# Sterownik_pralnia.net
KiCad netlist of a schematic drawn in EAGLE
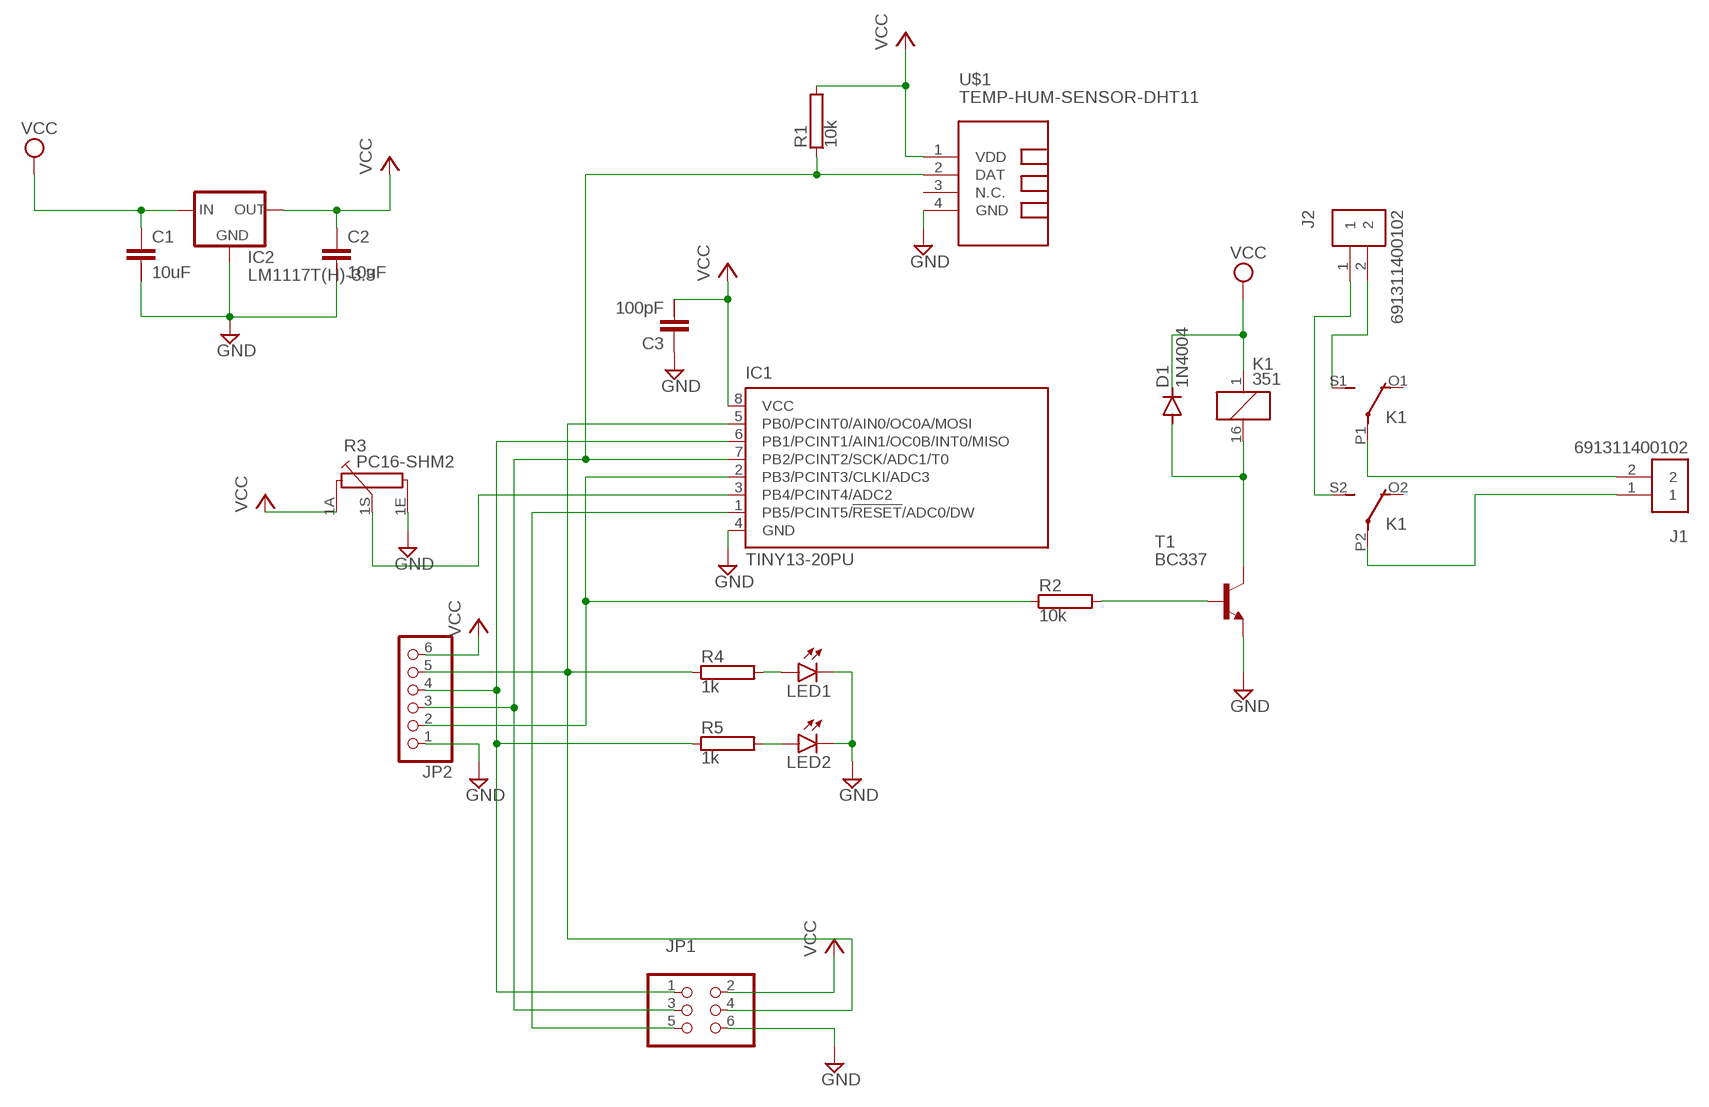
[diagram p0: schematic, sheet 1]

(export (version "E")
  (design (tool "Eeschema 10.0.6"))
  (components
    (comp (ref "C1")
      (value "10uF")
      (footprint "eagle-import:C2.5_5-2")
      (libsource (lib "eagle-import") (part "C-2.5-5/2"))
    )
    (comp (ref "C2")
      (value "10uF")
      (footprint "eagle-import:C2.5_5-2")
      (libsource (lib "eagle-import") (part "C-2.5-5/2"))
    )
    (comp (ref "C3")
      (value "100pF")
      (footprint "eagle-import:C2.5_5-2")
      (libsource (lib "eagle-import") (part "C-2.5-5/2"))
    )
    (comp (ref "D1")
      (value "1N4004")
      (footprint "eagle-import:DO41-10")
      (libsource (lib "eagle-import") (part "1N4004"))
    )
    (comp (ref "IC1")
      (value "TINY13-20PU")
      (footprint "eagle-import:DIL08")
      (fields (field (name "MPN") "ATTINY13-20PU"))
      (libsource (lib "eagle-import") (part "TINY13PU-20"))
    )
    (comp (ref "IC2")
      (value "LM1117T(H)-3.3")
      (footprint "eagle-import:TO220H")
      (fields (field (name "MF") "Texas Instruments") (field (name "MPN") "LM1117T-3.3"))
      (libsource (lib "eagle-import") (part "LM1117?-T(H)3.3"))
    )
    (comp (ref "J1")
      (value "691311400102")
      (footprint "eagle-import:TERMINALBLOCK_PLUGGABLE-2-7.62MM")
      (fields
        (field (name "DIGIKEY_PART_NO") "732-2823-ND")
        (field (name "MANUFACTURER") "WURTH ELEKTRONIK")
        (field (name "CREATED_BY") "PCBLayout.com")
      )
      (libsource (lib "eagle-import") (part "691311400102"))
    )
    (comp (ref "J2")
      (value "691311400102")
      (footprint "eagle-import:TERMINALBLOCK_PLUGGABLE-2-7.62MM")
      (fields
        (field (name "DIGIKEY_PART_NO") "732-2823-ND")
        (field (name "MANUFACTURER") "WURTH ELEKTRONIK")
        (field (name "CREATED_BY") "PCBLayout.com")
      )
      (libsource (lib "eagle-import") (part "691311400102"))
    )
    (comp (ref "JP1")
      (value "PINHD-2X3")
      (footprint "eagle-import:2X03")
      (libsource (lib "eagle-import") (part "PINHD-2X3"))
    )
    (comp (ref "JP2")
      (value "PINHD-1X6")
      (footprint "eagle-import:1X06")
      (libsource (lib "eagle-import") (part "PINHD-1X6"))
    )
    (comp (ref "K1")
      (value "351")
      (footprint "eagle-import:351")
      (libsource (lib "eagle-import") (part "351"))
    )
    (comp (ref "LED1")
      (value "LEDB152")
      (footprint "eagle-import:Q62902-B152")
      (libsource (lib "eagle-import") (part "LEDB152"))
    )
    (comp (ref "LED2")
      (value "LEDB152")
      (footprint "eagle-import:Q62902-B152")
      (libsource (lib "eagle-import") (part "LEDB152"))
    )
    (comp (ref "R1")
      (value "10k")
      (footprint "eagle-import:AC01")
      (libsource (lib "eagle-import") (part "RAC01"))
    )
    (comp (ref "R2")
      (value "10k")
      (footprint "eagle-import:AC01")
      (libsource (lib "eagle-import") (part "RAC01"))
    )
    (comp (ref "R3")
      (value "PC16-SHM2")
      (footprint "eagle-import:PC16-SHM2")
      (libsource (lib "eagle-import") (part "PC16-SHM2"))
    )
    (comp (ref "R4")
      (value "1k")
      (footprint "eagle-import:AC01")
      (libsource (lib "eagle-import") (part "RAC01"))
    )
    (comp (ref "R5")
      (value "1k")
      (footprint "eagle-import:AC01")
      (libsource (lib "eagle-import") (part "RAC01"))
    )
    (comp (ref "T1")
      (value "BC337")
      (footprint "eagle-import:TO92")
      (libsource (lib "eagle-import") (part "BC337"))
    )
    (comp (ref "U$1")
      (value "TEMP-HUM-SENSOR-DHT11")
      (footprint "eagle-import:TEMP-HUM-SENSOR-DHT11")
      (libsource (lib "eagle-import") (part "TEMP-HUM-SENSOR-DHT11"))
    )
  )
  (nets
    (net (code "1") (name "GND") (class "Default")
      (node (ref "C1") (pin "2") (pinfunction "2_2") (pintype "passive"))
      (node (ref "C2") (pin "2") (pinfunction "2_2") (pintype "passive"))
      (node (ref "C3") (pin "1") (pinfunction "1_1") (pintype "passive"))
      (node (ref "IC1") (pin "4") (pinfunction "GND_4") (pintype "power_in"))
      (node (ref "IC2") (pin "1") (pinfunction "GND_1") (pintype "input"))
      (node (ref "JP1") (pin "6") (pinfunction "6_6") (pintype "passive"))
      (node (ref "JP2") (pin "1") (pinfunction "1_1") (pintype "passive"))
      (node (ref "LED1") (pin "K") (pinfunction "C_K") (pintype "passive"))
      (node (ref "LED2") (pin "K") (pinfunction "C_K") (pintype "passive"))
      (node (ref "R3") (pin "1E") (pinfunction "1E_1E") (pintype "passive"))
      (node (ref "T1") (pin "1") (pinfunction "E_1") (pintype "passive"))
      (node (ref "U$1") (pin "4") (pinfunction "GND_4") (pintype "power_in"))
    )
    (net (code "2") (name "Net-(IC1-PB0{slash}PCINT0{slash}AIN0{slash}OC0A{slash}MOSI)") (class "Default")
      (node (ref "IC1") (pin "5") (pinfunction "PB0/PCINT0/AIN0/OC0A/MOSI_5") (pintype "bidirectional"))
      (node (ref "JP1") (pin "4") (pinfunction "4_4") (pintype "passive"))
      (node (ref "JP2") (pin "5") (pinfunction "5_5") (pintype "passive"))
      (node (ref "R4") (pin "1") (pinfunction "1_1") (pintype "passive"))
    )
    (net (code "3") (name "Net-(IC1-PB1{slash}PCINT1{slash}AIN1{slash}OC0B{slash}INT0{slash}MISO)") (class "Default")
      (node (ref "IC1") (pin "6") (pinfunction "PB1/PCINT1/AIN1/OC0B/INT0/MISO_6") (pintype "bidirectional"))
      (node (ref "JP1") (pin "1") (pinfunction "1_1") (pintype "passive"))
      (node (ref "JP2") (pin "4") (pinfunction "4_4") (pintype "passive"))
      (node (ref "R5") (pin "1") (pinfunction "1_1") (pintype "passive"))
    )
    (net (code "4") (name "Net-(IC1-PB2{slash}PCINT2{slash}SCK{slash}ADC1{slash}T0)") (class "Default")
      (node (ref "IC1") (pin "7") (pinfunction "PB2/PCINT2/SCK/ADC1/T0_7") (pintype "bidirectional"))
      (node (ref "JP1") (pin "3") (pinfunction "3_3") (pintype "passive"))
      (node (ref "JP2") (pin "3") (pinfunction "3_3") (pintype "passive"))
      (node (ref "R1") (pin "1") (pinfunction "1_1") (pintype "passive"))
      (node (ref "U$1") (pin "2") (pinfunction "DAT_2") (pintype "bidirectional"))
    )
    (net (code "5") (name "Net-(IC1-PB3{slash}PCINT3{slash}CLKI{slash}ADC3)") (class "Default")
      (node (ref "IC1") (pin "2") (pinfunction "PB3/PCINT3/CLKI/ADC3_2") (pintype "bidirectional"))
      (node (ref "JP2") (pin "2") (pinfunction "2_2") (pintype "passive"))
      (node (ref "R2") (pin "1") (pinfunction "1_1") (pintype "passive"))
    )
    (net (code "6") (name "Net-(IC1-PB4{slash}PCINT4{slash}ADC2)") (class "Default")
      (node (ref "IC1") (pin "3") (pinfunction "PB4/PCINT4/ADC2_3") (pintype "bidirectional"))
      (node (ref "R3") (pin "1S") (pinfunction "1S_1S") (pintype "passive"))
    )
    (net (code "7") (name "Net-(IC1-PB5{slash}PCINT5{slash}~{RESET}{slash}ADC0{slash}DW)") (class "Default")
      (node (ref "IC1") (pin "1") (pinfunction "PB5/PCINT5/~{RESET}/ADC0/DW_1") (pintype "bidirectional"))
      (node (ref "JP1") (pin "5") (pinfunction "5_5") (pintype "passive"))
    )
    (net (code "8") (name "Net-(K1A-2)") (class "Default")
      (node (ref "D1") (pin "A") (pinfunction "A_A") (pintype "passive"))
      (node (ref "K1") (pin "16") (pinfunction "2_16") (pintype "passive"))
      (node (ref "T1") (pin "3") (pinfunction "C_3") (pintype "passive"))
    )
    (net (code "9") (name "Net-(K1B-P)") (class "Default")
      (node (ref "J1") (pin "2") (pinfunction "2_2") (pintype "passive"))
      (node (ref "K1") (pin "P1") (pinfunction "P_P1") (pintype "passive"))
    )
    (net (code "10") (name "Net-(K1B-S)") (class "Default")
      (node (ref "J2") (pin "2") (pinfunction "2_2") (pintype "passive"))
      (node (ref "K1") (pin "S1") (pinfunction "S_S1") (pintype "passive"))
    )
    (net (code "11") (name "Net-(K1C-P)") (class "Default")
      (node (ref "J1") (pin "1") (pinfunction "1_1") (pintype "passive"))
      (node (ref "K1") (pin "P2") (pinfunction "P_P2") (pintype "passive"))
    )
    (net (code "12") (name "Net-(K1C-S)") (class "Default")
      (node (ref "J2") (pin "1") (pinfunction "1_1") (pintype "passive"))
      (node (ref "K1") (pin "S2") (pinfunction "S_S2") (pintype "passive"))
    )
    (net (code "13") (name "Net-(LED1-PadA)") (class "Default")
      (node (ref "LED1") (pin "A") (pinfunction "A_A") (pintype "passive"))
      (node (ref "R4") (pin "2") (pinfunction "2_2") (pintype "passive"))
    )
    (net (code "14") (name "Net-(LED2-PadA)") (class "Default")
      (node (ref "LED2") (pin "A") (pinfunction "A_A") (pintype "passive"))
      (node (ref "R5") (pin "2") (pinfunction "2_2") (pintype "passive"))
    )
    (net (code "15") (name "Net-(T1-B)") (class "Default")
      (node (ref "R2") (pin "2") (pinfunction "2_2") (pintype "passive"))
      (node (ref "T1") (pin "2") (pinfunction "B_2") (pintype "passive"))
    )
    (net (code "16") (name "VCC") (class "Default")
      (node (ref "C1") (pin "1") (pinfunction "1_1") (pintype "passive"))
      (node (ref "C2") (pin "1") (pinfunction "1_1") (pintype "passive"))
      (node (ref "C3") (pin "2") (pinfunction "2_2") (pintype "passive"))
      (node (ref "D1") (pin "C") (pinfunction "C_C") (pintype "passive"))
      (node (ref "IC1") (pin "8") (pinfunction "VCC_8") (pintype "power_in"))
      (node (ref "IC2") (pin "2") (pinfunction "OUT_2") (pintype "passive"))
      (node (ref "IC2") (pin "3") (pinfunction "IN_3") (pintype "input"))
      (node (ref "JP1") (pin "2") (pinfunction "2_2") (pintype "passive"))
      (node (ref "JP2") (pin "6") (pinfunction "6_6") (pintype "passive"))
      (node (ref "K1") (pin "1") (pinfunction "1_1") (pintype "passive"))
      (node (ref "R1") (pin "2") (pinfunction "2_2") (pintype "passive"))
      (node (ref "R3") (pin "1A") (pinfunction "1A_1A") (pintype "passive"))
      (node (ref "U$1") (pin "1") (pinfunction "VDD_1") (pintype "power_in"))
    )
    (net (code "17") (name "unconnected-(C1-Pad3)") (class "Default")
      (node (ref "C1") (pin "3") (pinfunction "3_3") (pintype "passive"))
    )
    (net (code "18") (name "unconnected-(C2-Pad3)") (class "Default")
      (node (ref "C2") (pin "3") (pinfunction "3_3") (pintype "passive"))
    )
    (net (code "19") (name "unconnected-(C3-Pad3)") (class "Default")
      (node (ref "C3") (pin "3") (pinfunction "3_3") (pintype "passive"))
    )
    (net (code "20") (name "unconnected-(K1B-O-PadO1)") (class "Default")
      (node (ref "K1") (pin "O1") (pinfunction "O_O1") (pintype "passive"))
    )
    (net (code "21") (name "unconnected-(K1C-O-PadO2)") (class "Default")
      (node (ref "K1") (pin "O2") (pinfunction "O_O2") (pintype "passive"))
    )
    (net (code "22") (name "unconnected-(U$1-N.C.-Pad3)") (class "Default")
      (node (ref "U$1") (pin "3") (pinfunction "N.C._3") (pintype "passive"))
    )
  )
)
